# main.net
KiCad netlist of a schematic drawn in EAGLE
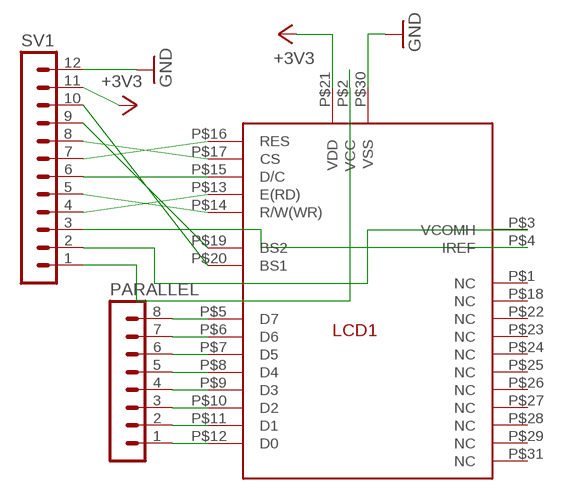
[diagram p0: schematic, sheet 1]

(export (version "E")
  (design (tool "Eeschema 10.0.6"))
  (components
    (comp (ref "LCD1")
      (value "SSD1306")
      (footprint "eagle-import:SSD1306")
      (libsource (lib "eagle-import") (part "SSD1306"))
    )
    (comp (ref "PARALLEL")
      (value "MA08-1")
      (footprint "eagle-import:MA08-1")
      (libsource (lib "eagle-import") (part "MA08-1"))
    )
    (comp (ref "SV1")
      (value "MA12-1")
      (footprint "eagle-import:MA12-1")
      (libsource (lib "eagle-import") (part "MA12-1"))
    )
  )
  (nets
    (net (code "1") (name "+3V3") (class "Default")
      (node (ref "LCD1") (pin "P$21") (pinfunction "VDD_P$21") (pintype "input"))
      (node (ref "SV1") (pin "11") (pinfunction "11_11") (pintype "passive"))
    )
    (net (code "2") (name "GND") (class "Default")
      (node (ref "LCD1") (pin "P$30") (pinfunction "VSS_P$30") (pintype "input"))
      (node (ref "SV1") (pin "12") (pinfunction "12_12") (pintype "passive"))
    )
    (net (code "3") (name "Net-(LCD1-BS1)") (class "Default")
      (node (ref "LCD1") (pin "P$20") (pinfunction "BS1_P$20") (pintype "input"))
      (node (ref "SV1") (pin "10") (pinfunction "10_10") (pintype "passive"))
    )
    (net (code "4") (name "Net-(LCD1-BS2)") (class "Default")
      (node (ref "LCD1") (pin "P$19") (pinfunction "BS2_P$19") (pintype "input"))
      (node (ref "SV1") (pin "9") (pinfunction "9_9") (pintype "passive"))
    )
    (net (code "5") (name "Net-(LCD1-CS)") (class "Default")
      (node (ref "LCD1") (pin "P$17") (pinfunction "CS_P$17") (pintype "input"))
      (node (ref "SV1") (pin "8") (pinfunction "8_8") (pintype "passive"))
    )
    (net (code "6") (name "Net-(LCD1-D0)") (class "Default")
      (node (ref "LCD1") (pin "P$12") (pinfunction "D0_P$12") (pintype "bidirectional"))
      (node (ref "PARALLEL") (pin "1") (pinfunction "1_1") (pintype "passive"))
    )
    (net (code "7") (name "Net-(LCD1-D1)") (class "Default")
      (node (ref "LCD1") (pin "P$11") (pinfunction "D1_P$11") (pintype "bidirectional"))
      (node (ref "PARALLEL") (pin "2") (pinfunction "2_2") (pintype "passive"))
    )
    (net (code "8") (name "Net-(LCD1-D2)") (class "Default")
      (node (ref "LCD1") (pin "P$10") (pinfunction "D2_P$10") (pintype "bidirectional"))
      (node (ref "PARALLEL") (pin "3") (pinfunction "3_3") (pintype "passive"))
    )
    (net (code "9") (name "Net-(LCD1-D3)") (class "Default")
      (node (ref "LCD1") (pin "P$9") (pinfunction "D3_P$9") (pintype "bidirectional"))
      (node (ref "PARALLEL") (pin "4") (pinfunction "4_4") (pintype "passive"))
    )
    (net (code "10") (name "Net-(LCD1-D4)") (class "Default")
      (node (ref "LCD1") (pin "P$8") (pinfunction "D4_P$8") (pintype "bidirectional"))
      (node (ref "PARALLEL") (pin "5") (pinfunction "5_5") (pintype "passive"))
    )
    (net (code "11") (name "Net-(LCD1-D5)") (class "Default")
      (node (ref "LCD1") (pin "P$7") (pinfunction "D5_P$7") (pintype "bidirectional"))
      (node (ref "PARALLEL") (pin "6") (pinfunction "6_6") (pintype "passive"))
    )
    (net (code "12") (name "Net-(LCD1-D6)") (class "Default")
      (node (ref "LCD1") (pin "P$6") (pinfunction "D6_P$6") (pintype "bidirectional"))
      (node (ref "PARALLEL") (pin "7") (pinfunction "7_7") (pintype "passive"))
    )
    (net (code "13") (name "Net-(LCD1-D7)") (class "Default")
      (node (ref "LCD1") (pin "P$5") (pinfunction "D7_P$5") (pintype "bidirectional"))
      (node (ref "PARALLEL") (pin "8") (pinfunction "8_8") (pintype "passive"))
    )
    (net (code "14") (name "Net-(LCD1-D{slash}C)") (class "Default")
      (node (ref "LCD1") (pin "P$15") (pinfunction "D/C_P$15") (pintype "input"))
      (node (ref "SV1") (pin "6") (pinfunction "6_6") (pintype "passive"))
    )
    (net (code "15") (name "Net-(LCD1-E(RD))") (class "Default")
      (node (ref "LCD1") (pin "P$13") (pinfunction "E(RD)_P$13") (pintype "input"))
      (node (ref "SV1") (pin "4") (pinfunction "4_4") (pintype "passive"))
    )
    (net (code "16") (name "Net-(LCD1-IREF)") (class "Default")
      (node (ref "LCD1") (pin "P$4") (pinfunction "IREF_P$4") (pintype "input"))
      (node (ref "SV1") (pin "3") (pinfunction "3_3") (pintype "passive"))
    )
    (net (code "17") (name "Net-(LCD1-RES)") (class "Default")
      (node (ref "LCD1") (pin "P$16") (pinfunction "RES_P$16") (pintype "input"))
      (node (ref "SV1") (pin "7") (pinfunction "7_7") (pintype "passive"))
    )
    (net (code "18") (name "Net-(LCD1-R{slash}W(WR))") (class "Default")
      (node (ref "LCD1") (pin "P$14") (pinfunction "R/W(WR)_P$14") (pintype "input"))
      (node (ref "SV1") (pin "5") (pinfunction "5_5") (pintype "passive"))
    )
    (net (code "19") (name "Net-(LCD1-VCC)") (class "Default")
      (node (ref "LCD1") (pin "P$2") (pinfunction "VCC_P$2") (pintype "input"))
      (node (ref "SV1") (pin "1") (pinfunction "1_1") (pintype "passive"))
    )
    (net (code "20") (name "Net-(LCD1-VCOMH)") (class "Default")
      (node (ref "LCD1") (pin "P$3") (pinfunction "VCOMH_P$3") (pintype "output"))
      (node (ref "SV1") (pin "2") (pinfunction "2_2") (pintype "passive"))
    )
    (net (code "21") (name "unconnected-(LCD1-NC-PadP$1)") (class "Default")
      (node (ref "LCD1") (pin "P$1") (pinfunction "NC_P$1") (pintype "input"))
    )
    (net (code "22") (name "unconnected-(LCD1-NC-PadP$18)") (class "Default")
      (node (ref "LCD1") (pin "P$18") (pinfunction "NC_P$18") (pintype "input"))
    )
    (net (code "23") (name "unconnected-(LCD1-NC-PadP$22)") (class "Default")
      (node (ref "LCD1") (pin "P$22") (pinfunction "NC_P$22") (pintype "input"))
    )
    (net (code "24") (name "unconnected-(LCD1-NC-PadP$23)") (class "Default")
      (node (ref "LCD1") (pin "P$23") (pinfunction "NC_P$23") (pintype "input"))
    )
    (net (code "25") (name "unconnected-(LCD1-NC-PadP$24)") (class "Default")
      (node (ref "LCD1") (pin "P$24") (pinfunction "NC_P$24") (pintype "input"))
    )
    (net (code "26") (name "unconnected-(LCD1-NC-PadP$25)") (class "Default")
      (node (ref "LCD1") (pin "P$25") (pinfunction "NC_P$25") (pintype "input"))
    )
    (net (code "27") (name "unconnected-(LCD1-NC-PadP$26)") (class "Default")
      (node (ref "LCD1") (pin "P$26") (pinfunction "NC_P$26") (pintype "input"))
    )
    (net (code "28") (name "unconnected-(LCD1-NC-PadP$27)") (class "Default")
      (node (ref "LCD1") (pin "P$27") (pinfunction "NC_P$27") (pintype "input"))
    )
    (net (code "29") (name "unconnected-(LCD1-NC-PadP$28)") (class "Default")
      (node (ref "LCD1") (pin "P$28") (pinfunction "NC_P$28") (pintype "input"))
    )
    (net (code "30") (name "unconnected-(LCD1-NC-PadP$29)") (class "Default")
      (node (ref "LCD1") (pin "P$29") (pinfunction "NC_P$29") (pintype "input"))
    )
    (net (code "31") (name "unconnected-(LCD1-NC-PadP$31)") (class "Default")
      (node (ref "LCD1") (pin "P$31") (pinfunction "NC_P$31") (pintype "input"))
    )
  )
)
